# main.net
KiCad netlist of a schematic drawn in EAGLE
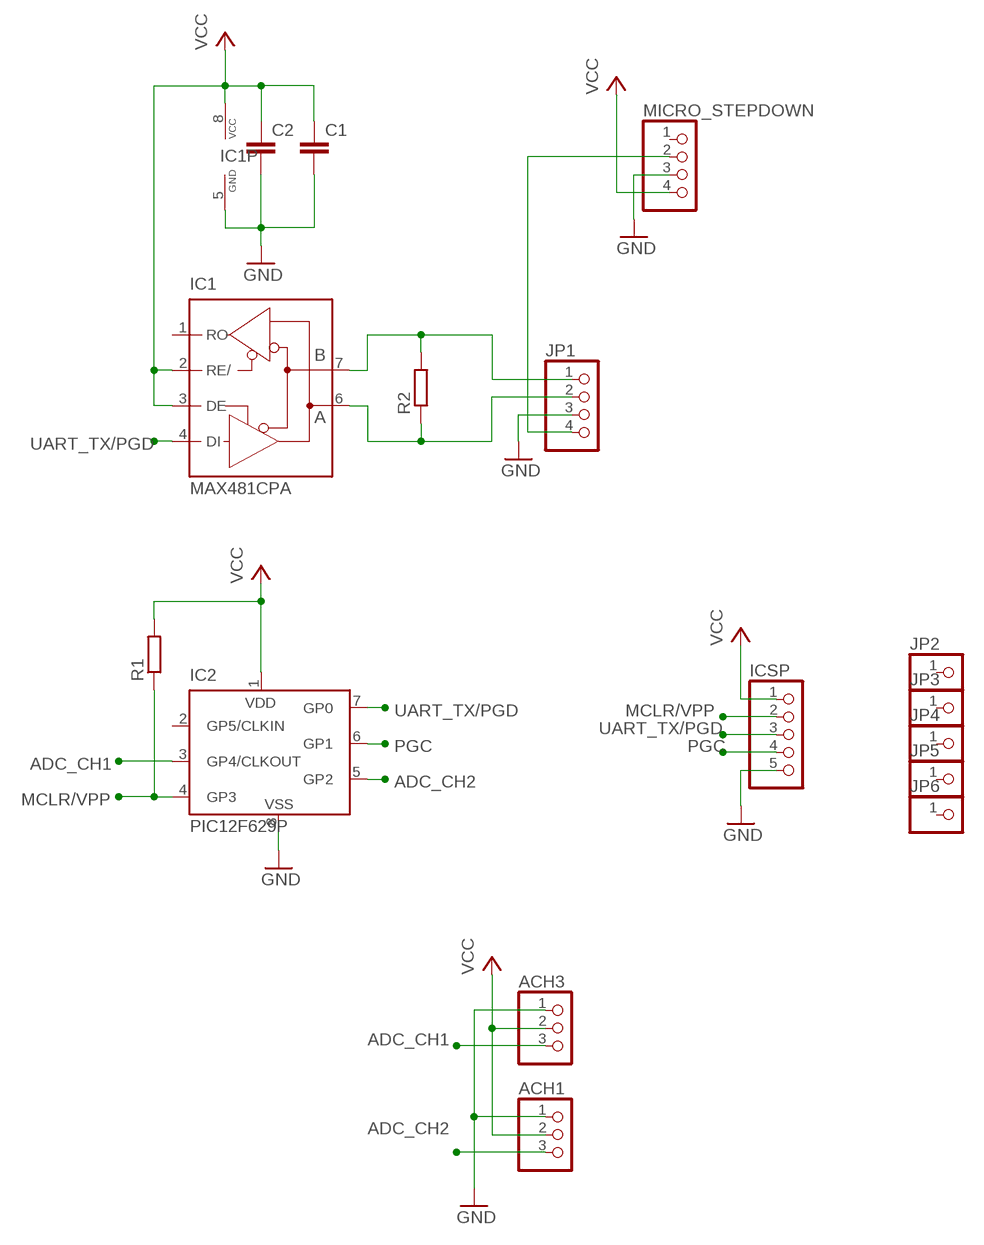
[diagram p0: schematic, sheet 1]

(export (version "E")
  (design (tool "Eeschema 10.0.6"))
  (components
    (comp (ref "ACH1")
      (value "PINHD-1X3")
      (footprint "eagle-import:1X03")
      (libsource (lib "eagle-import") (part "PINHD-1X3"))
    )
    (comp (ref "ACH3")
      (value "PINHD-1X3")
      (footprint "eagle-import:1X03")
      (libsource (lib "eagle-import") (part "PINHD-1X3"))
    )
    (comp (ref "C1")
      (value "C-EUC0603")
      (footprint "eagle-import:C0603")
      (libsource (lib "eagle-import") (part "C-EUC0603"))
    )
    (comp (ref "C2")
      (value "C-EUC0603")
      (footprint "eagle-import:C0603")
      (libsource (lib "eagle-import") (part "C-EUC0603"))
    )
    (comp (ref "IC1")
      (value "MAX481CPA")
      (footprint "eagle-import:DIL08")
      (fields (field (name "MPN") "MAX481CPA+"))
      (libsource (lib "eagle-import") (part "MAX481CPA"))
    )
    (comp (ref "IC2")
      (value "PIC12F629P")
      (footprint "eagle-import:DIL8")
      (fields (field (name "MF") "MICROCHIP") (field (name "MPN") "PIC12F629-I/P"))
      (libsource (lib "eagle-import") (part "PIC12F6P29"))
    )
    (comp (ref "ICSP")
      (value "PINHD-1X5")
      (footprint "eagle-import:1X05")
      (libsource (lib "eagle-import") (part "PINHD-1X5"))
    )
    (comp (ref "JP1")
      (value "PINHD-1X4")
      (footprint "eagle-import:1X04")
      (libsource (lib "eagle-import") (part "PINHD-1X4"))
    )
    (comp (ref "JP2")
      (value "PINHD-1X1")
      (footprint "eagle-import:1X01")
      (libsource (lib "eagle-import") (part "PINHD-1X1"))
    )
    (comp (ref "JP3")
      (value "PINHD-1X1")
      (footprint "eagle-import:1X01")
      (libsource (lib "eagle-import") (part "PINHD-1X1"))
    )
    (comp (ref "JP4")
      (value "PINHD-1X1")
      (footprint "eagle-import:1X01")
      (libsource (lib "eagle-import") (part "PINHD-1X1"))
    )
    (comp (ref "JP5")
      (value "PINHD-1X1")
      (footprint "eagle-import:1X01")
      (libsource (lib "eagle-import") (part "PINHD-1X1"))
    )
    (comp (ref "JP6")
      (value "PINHD-1X1")
      (footprint "eagle-import:1X01")
      (libsource (lib "eagle-import") (part "PINHD-1X1"))
    )
    (comp (ref "MICRO_STEPDOWN")
      (value "PINHD-1X4/90")
      (footprint "eagle-import:1X04_90")
      (libsource (lib "eagle-import") (part "PINHD-1X4/90"))
    )
    (comp (ref "R1")
      (value "R-EU_R0603")
      (footprint "eagle-import:R0603")
      (libsource (lib "eagle-import") (part "R-EU_R0603"))
    )
    (comp (ref "R2")
      (value "R-EU_R0603")
      (footprint "eagle-import:R0603")
      (libsource (lib "eagle-import") (part "R-EU_R0603"))
    )
  )
  (nets
    (net (code "1") (name "/ADC_CH1") (class "Default")
      (node (ref "ACH3") (pin "3") (pinfunction "3_3") (pintype "passive"))
      (node (ref "IC2") (pin "3") (pinfunction "GP4/CLKOUT_3") (pintype "bidirectional"))
    )
    (net (code "2") (name "/ADC_CH2") (class "Default")
      (node (ref "ACH1") (pin "3") (pinfunction "3_3") (pintype "passive"))
      (node (ref "IC2") (pin "5") (pinfunction "GP2_5") (pintype "bidirectional"))
    )
    (net (code "3") (name "/MCLR{slash}VPP") (class "Default")
      (node (ref "IC2") (pin "4") (pinfunction "GP3_4") (pintype "input"))
      (node (ref "ICSP") (pin "2") (pinfunction "2_2") (pintype "passive"))
      (node (ref "R1") (pin "1") (pinfunction "1_1") (pintype "passive"))
    )
    (net (code "4") (name "/PGC") (class "Default")
      (node (ref "IC2") (pin "6") (pinfunction "GP1_6") (pintype "bidirectional"))
      (node (ref "ICSP") (pin "4") (pinfunction "4_4") (pintype "passive"))
    )
    (net (code "5") (name "/UART_TX{slash}PGD") (class "Default")
      (node (ref "IC1") (pin "4") (pinfunction "DI_4") (pintype "input"))
      (node (ref "IC2") (pin "7") (pinfunction "GP0_7") (pintype "bidirectional"))
      (node (ref "ICSP") (pin "3") (pinfunction "3_3") (pintype "passive"))
    )
    (net (code "6") (name "GND") (class "Default")
      (node (ref "ACH1") (pin "1") (pinfunction "1_1") (pintype "passive"))
      (node (ref "ACH3") (pin "1") (pinfunction "1_1") (pintype "passive"))
      (node (ref "C1") (pin "2") (pinfunction "2_2") (pintype "passive"))
      (node (ref "C2") (pin "2") (pinfunction "2_2") (pintype "passive"))
      (node (ref "IC1") (pin "5") (pinfunction "GND_5") (pintype "power_in"))
      (node (ref "IC2") (pin "8") (pinfunction "VSS_8") (pintype "power_in"))
      (node (ref "ICSP") (pin "5") (pinfunction "5_5") (pintype "passive"))
      (node (ref "JP1") (pin "3") (pinfunction "3_3") (pintype "passive"))
      (node (ref "MICRO_STEPDOWN") (pin "3") (pinfunction "3_3") (pintype "passive"))
    )
    (net (code "7") (name "Net-(IC1A-A)") (class "Default")
      (node (ref "IC1") (pin "6") (pinfunction "A_6") (pintype "passive"))
      (node (ref "JP1") (pin "2") (pinfunction "2_2") (pintype "passive"))
      (node (ref "R2") (pin "1") (pinfunction "1_1") (pintype "passive"))
    )
    (net (code "8") (name "Net-(IC1A-B)") (class "Default")
      (node (ref "IC1") (pin "7") (pinfunction "B_7") (pintype "passive"))
      (node (ref "JP1") (pin "1") (pinfunction "1_1") (pintype "passive"))
      (node (ref "R2") (pin "2") (pinfunction "2_2") (pintype "passive"))
    )
    (net (code "9") (name "Net-(JP1-Pad4)") (class "Default")
      (node (ref "JP1") (pin "4") (pinfunction "4_4") (pintype "passive"))
      (node (ref "MICRO_STEPDOWN") (pin "2") (pinfunction "2_2") (pintype "passive"))
    )
    (net (code "10") (name "VCC") (class "Default")
      (node (ref "ACH1") (pin "2") (pinfunction "2_2") (pintype "passive"))
      (node (ref "ACH3") (pin "2") (pinfunction "2_2") (pintype "passive"))
      (node (ref "C1") (pin "1") (pinfunction "1_1") (pintype "passive"))
      (node (ref "C2") (pin "1") (pinfunction "1_1") (pintype "passive"))
      (node (ref "IC1") (pin "2") (pinfunction "RE/_2") (pintype "input"))
      (node (ref "IC1") (pin "3") (pinfunction "DE_3") (pintype "input"))
      (node (ref "IC1") (pin "8") (pinfunction "VCC_8") (pintype "power_in"))
      (node (ref "IC2") (pin "1") (pinfunction "VDD_1") (pintype "power_in"))
      (node (ref "ICSP") (pin "1") (pinfunction "1_1") (pintype "passive"))
      (node (ref "MICRO_STEPDOWN") (pin "4") (pinfunction "4_4") (pintype "passive"))
      (node (ref "R1") (pin "2") (pinfunction "2_2") (pintype "passive"))
    )
    (net (code "11") (name "unconnected-(IC1A-RO-Pad1)") (class "Default")
      (node (ref "IC1") (pin "1") (pinfunction "RO_1") (pintype "output"))
    )
    (net (code "12") (name "unconnected-(IC2-GP5{slash}CLKIN-Pad2)") (class "Default")
      (node (ref "IC2") (pin "2") (pinfunction "GP5/CLKIN_2") (pintype "bidirectional"))
    )
    (net (code "13") (name "unconnected-(JP2-Pad1)") (class "Default")
      (node (ref "JP2") (pin "1") (pinfunction "1_1") (pintype "passive"))
    )
    (net (code "14") (name "unconnected-(JP3-Pad1)") (class "Default")
      (node (ref "JP3") (pin "1") (pinfunction "1_1") (pintype "passive"))
    )
    (net (code "15") (name "unconnected-(JP4-Pad1)") (class "Default")
      (node (ref "JP4") (pin "1") (pinfunction "1_1") (pintype "passive"))
    )
    (net (code "16") (name "unconnected-(JP5-Pad1)") (class "Default")
      (node (ref "JP5") (pin "1") (pinfunction "1_1") (pintype "passive"))
    )
    (net (code "17") (name "unconnected-(JP6-Pad1)") (class "Default")
      (node (ref "JP6") (pin "1") (pinfunction "1_1") (pintype "passive"))
    )
    (net (code "18") (name "unconnected-(MICRO_STEPDOWN-Pad1)") (class "Default")
      (node (ref "MICRO_STEPDOWN") (pin "1") (pinfunction "1_1") (pintype "passive"))
    )
  )
)
